# Sheet1.net
KiCad netlist of a schematic drawn in Altium Designer
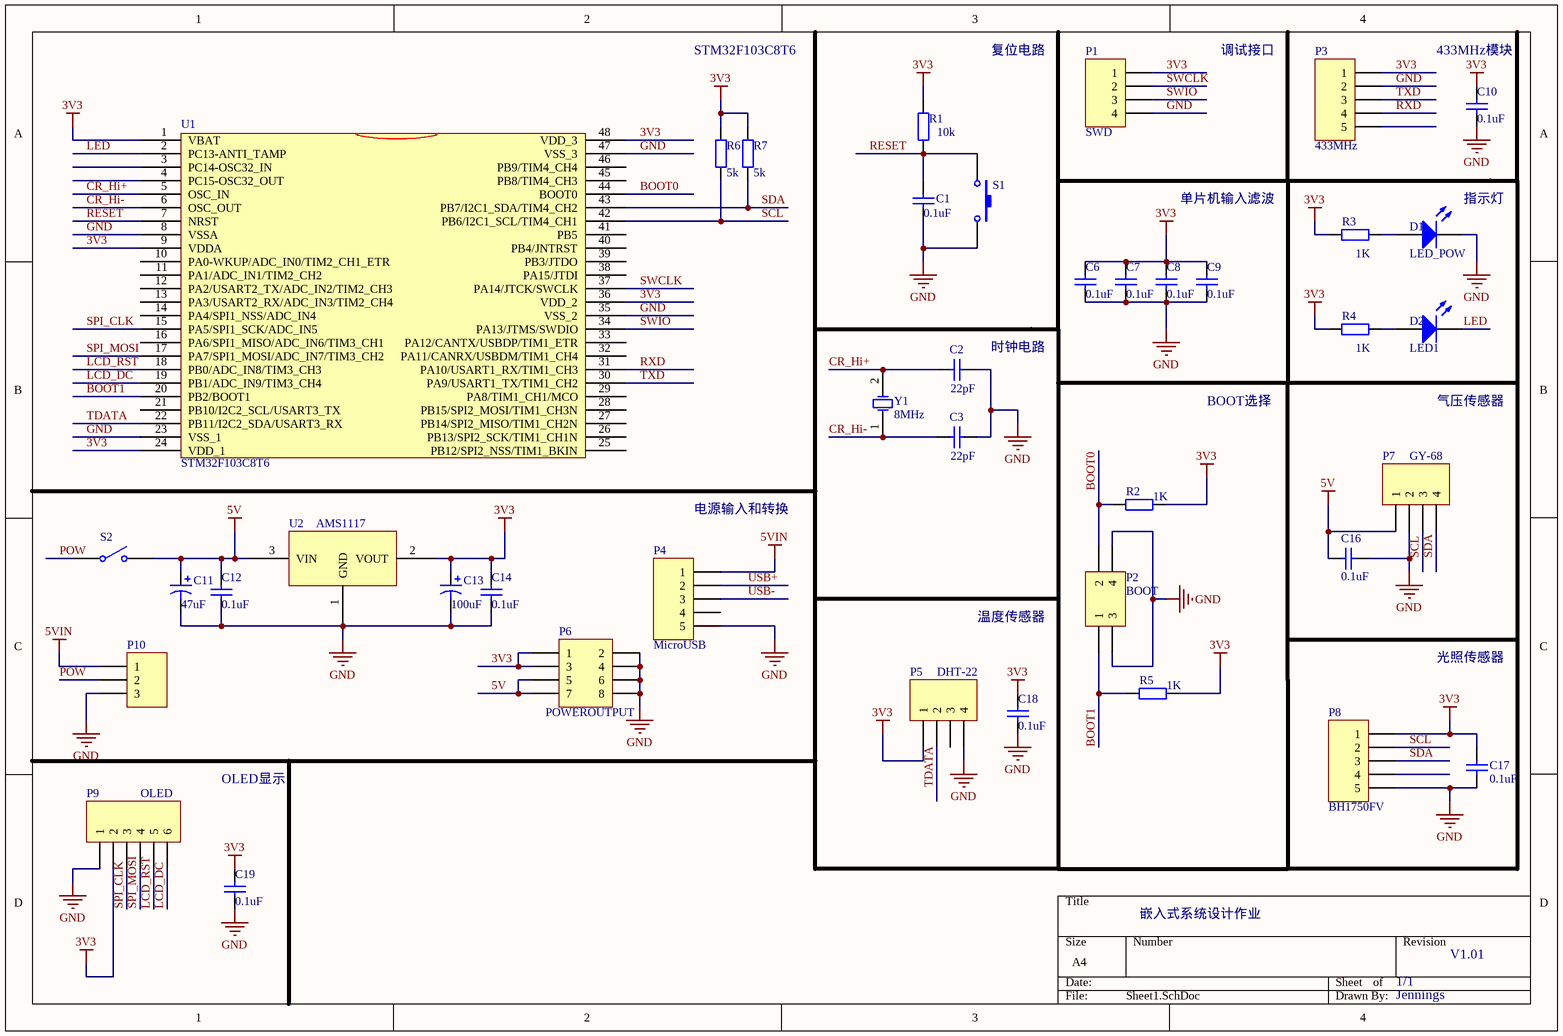
[diagram p0: Sheet1.SchDoc]

(export (version "E")
  (design (tool "Eeschema 10.0.6"))
  (components
    (comp (ref "C1")
      (value "0.1uF")
      (footprint "0402")
      (description "Capacitor")
      (fields (field (name "Comment") "Cap") (field (name "PUBLISHER") "Altium Limited"))
      (libsource (lib "Miscellaneous Devices") (part "Cap"))
    )
    (comp (ref "C2")
      (value "22pF")
      (footprint "0603-1")
      (description "Capacitor")
      (fields (field (name "Comment") "Cap") (field (name "PUBLISHER") "Altium Limited"))
      (libsource (lib "Miscellaneous Devices") (part "Cap"))
    )
    (comp (ref "C3")
      (value "22pF")
      (footprint "0603-1")
      (description "Capacitor")
      (fields (field (name "Comment") "Cap") (field (name "PUBLISHER") "Altium Limited"))
      (libsource (lib "Miscellaneous Devices") (part "Cap"))
    )
    (comp (ref "C6")
      (value "0.1uF")
      (footprint "0402")
      (description "Capacitor")
      (fields (field (name "Comment") "Cap") (field (name "PUBLISHER") "Altium Limited"))
      (libsource (lib "Miscellaneous Devices") (part "Cap"))
    )
    (comp (ref "C7")
      (value "0.1uF")
      (footprint "0402")
      (description "Capacitor")
      (fields (field (name "Comment") "Cap") (field (name "PUBLISHER") "Altium Limited"))
      (libsource (lib "Miscellaneous Devices") (part "Cap"))
    )
    (comp (ref "C8")
      (value "0.1uF")
      (footprint "0402")
      (description "Capacitor")
      (fields (field (name "Comment") "Cap") (field (name "PUBLISHER") "Altium Limited"))
      (libsource (lib "Miscellaneous Devices") (part "Cap"))
    )
    (comp (ref "C9")
      (value "0.1uF")
      (footprint "0402")
      (description "Capacitor")
      (fields (field (name "Comment") "Cap") (field (name "PUBLISHER") "Altium Limited"))
      (libsource (lib "Miscellaneous Devices") (part "Cap"))
    )
    (comp (ref "C10")
      (value "0.1uF")
      (footprint "0402")
      (description "Capacitor")
      (fields (field (name "Comment") "Cap") (field (name "PUBLISHER") "Altium Limited"))
      (libsource (lib "Miscellaneous Devices") (part "Cap"))
    )
    (comp (ref "C11")
      (value "47uF")
      (footprint "CAP-7343")
      (description "Polarized Capacitor (Radial)")
      (fields (field (name "Comment") "Cap Pol1") (field (name "PUBLISHER") "Altium Limited"))
      (libsource (lib "Miscellaneous Devices") (part "Cap Pol1"))
    )
    (comp (ref "C12")
      (value "0.1uF")
      (footprint "0402")
      (description "Capacitor")
      (fields (field (name "Comment") "Cap") (field (name "PUBLISHER") "Altium Limited"))
      (libsource (lib "Miscellaneous Devices") (part "Cap"))
    )
    (comp (ref "C13")
      (value "100uF")
      (footprint "CAP-6032")
      (description "Polarized Capacitor (Radial)")
      (fields (field (name "Comment") "Cap Pol1") (field (name "PUBLISHER") "Altium Limited"))
      (libsource (lib "Miscellaneous Devices") (part "Cap Pol1"))
    )
    (comp (ref "C14")
      (value "0.1uF")
      (footprint "0402")
      (description "Capacitor")
      (fields (field (name "Comment") "Cap") (field (name "PUBLISHER") "Altium Limited"))
      (libsource (lib "Miscellaneous Devices") (part "Cap"))
    )
    (comp (ref "C16")
      (value "0.1uF")
      (footprint "0402")
      (description "Capacitor")
      (fields (field (name "Comment") "Cap") (field (name "PUBLISHER") "Altium Limited"))
      (libsource (lib "Miscellaneous Devices") (part "Cap"))
    )
    (comp (ref "C17")
      (value "0.1uF")
      (footprint "0402")
      (description "Capacitor")
      (fields (field (name "Comment") "Cap") (field (name "PUBLISHER") "Altium Limited"))
      (libsource (lib "Miscellaneous Devices") (part "Cap"))
    )
    (comp (ref "C18")
      (value "0.1uF")
      (footprint "0402")
      (description "Capacitor")
      (fields (field (name "Comment") "Cap") (field (name "PUBLISHER") "Altium Limited"))
      (libsource (lib "Miscellaneous Devices") (part "Cap"))
    )
    (comp (ref "C19")
      (value "0.1uF")
      (footprint "0402")
      (description "Capacitor")
      (fields (field (name "Comment") "Cap") (field (name "PUBLISHER") "Altium Limited"))
      (libsource (lib "Miscellaneous Devices") (part "Cap"))
    )
    (comp (ref "D1")
      (value "LED_POW")
      (footprint "0402")
      (description "Typical RED, GREEN, YELLOW, AMBER GaAs LED")
      (fields (field (name "PUBLISHER") "Altium Limited"))
      (libsource (lib "Miscellaneous Devices") (part "LED2"))
    )
    (comp (ref "D2")
      (value "LED1")
      (footprint "0402")
      (description "Typical RED, GREEN, YELLOW, AMBER GaAs LED")
      (fields (field (name "PUBLISHER") "Altium Limited"))
      (libsource (lib "Miscellaneous Devices") (part "LED2"))
    )
    (comp (ref "P1")
      (value "SWD")
      (footprint "HDR1X4")
      (description "Header, 4-Pin")
      (fields (field (name "PUBLISHER") "Altium Limited"))
      (libsource (lib "Miscellaneous Connectors") (part "Header 4"))
    )
    (comp (ref "P2")
      (value "BOOT")
      (footprint "HDR2X2")
      (description "Header, 2-Pin, Dual row")
      (fields (field (name "PUBLISHER") "Altium Limited"))
      (libsource (lib "Miscellaneous Connectors") (part "Header 2X2"))
    )
    (comp (ref "P3")
      (value "433MHz")
      (footprint "HDR1X5")
      (description "Header, 5-Pin")
      (fields (field (name "PUBLISHER") "Altium Limited"))
      (libsource (lib "Miscellaneous Connectors") (part "Header 5"))
    )
    (comp (ref "P4")
      (value "MicroUSB")
      (footprint "Micro USB:Micro_USB")
      (description "Header, 5-Pin")
      (fields (field (name "PUBLISHER") "Altium Limited"))
      (libsource (lib "Miscellaneous Connectors") (part "Header 5"))
    )
    (comp (ref "P5")
      (value "DHT-22")
      (footprint "DHT22")
      (description "Header, 4-Pin")
      (fields (field (name "PUBLISHER") "Altium Limited"))
      (libsource (lib "") (part "Header 4_1"))
    )
    (comp (ref "P6")
      (value "POWEROUTPUT")
      (footprint "HDR2X4")
      (description "Header, 4-Pin, Dual row")
      (fields (field (name "PUBLISHER") "Altium Limited"))
      (libsource (lib "Miscellaneous Connectors") (part "Header 4X2"))
    )
    (comp (ref "P7")
      (value "GY-68")
      (footprint "BMP180MD")
      (description "Header, 4-Pin")
      (fields (field (name "PUBLISHER") "Altium Limited"))
      (libsource (lib "") (part "Header 4_1"))
    )
    (comp (ref "P8")
      (value "BH1750FV")
      (footprint "GY-30MD")
      (description "Header, 5-Pin")
      (fields (field (name "PUBLISHER") "Altium Limited"))
      (libsource (lib "Miscellaneous Connectors") (part "Header 5"))
    )
    (comp (ref "P9")
      (value "OLED")
      (footprint "OLED0.96")
      (description "Header, 6-Pin")
      (fields (field (name "PUBLISHER") "Altium Limited"))
      (libsource (lib "Miscellaneous Connectors") (part "Header 6"))
    )
    (comp (ref "P10")
      (value "Header 3")
      (footprint "HDR1X3")
      (description "Header, 3-Pin")
      (fields (field (name "PUBLISHER") "Altium Limited"))
      (libsource (lib "Miscellaneous Connectors") (part "Header 3"))
    )
    (comp (ref "R1")
      (value "10k")
      (footprint "0603-1")
      (description "Resistor")
      (fields (field (name "Comment") "Res2") (field (name "PUBLISHER") "Altium Limited"))
      (libsource (lib "") (part "Res2_1"))
    )
    (comp (ref "R2")
      (value "1K")
      (footprint "0402")
      (description "Resistor")
      (fields (field (name "Comment") "Res2") (field (name "PUBLISHER") "Altium Limited"))
      (libsource (lib "Miscellaneous Devices") (part "Res2"))
    )
    (comp (ref "R3")
      (value "1K")
      (footprint "0402")
      (description "Resistor")
      (fields (field (name "Comment") "Res2") (field (name "PUBLISHER") "Altium Limited"))
      (libsource (lib "Miscellaneous Devices") (part "Res2"))
    )
    (comp (ref "R4")
      (value "1K")
      (footprint "0402")
      (description "Resistor")
      (fields (field (name "Comment") "Res2") (field (name "PUBLISHER") "Altium Limited"))
      (libsource (lib "Miscellaneous Devices") (part "Res2"))
    )
    (comp (ref "R5")
      (value "1K")
      (footprint "0402")
      (description "Resistor")
      (fields (field (name "Comment") "Res2") (field (name "PUBLISHER") "Altium Limited"))
      (libsource (lib "Miscellaneous Devices") (part "Res2"))
    )
    (comp (ref "R6")
      (value "5k")
      (footprint "0603-1")
      (description "Resistor")
      (fields (field (name "Comment") "Res2") (field (name "PUBLISHER") "Altium Limited"))
      (libsource (lib "") (part "Res2_1"))
    )
    (comp (ref "R7")
      (value "5k")
      (footprint "0603-1")
      (description "Resistor")
      (fields (field (name "Comment") "Res2") (field (name "PUBLISHER") "Altium Limited"))
      (libsource (lib "") (part "Res2_1"))
    )
    (comp (ref "S1")
      (value "SW-PB")
      (footprint "SW_PB4_A1")
      (description "Switch")
      (fields (field (name "PUBLISHER") "Altium Limited"))
      (libsource (lib "Miscellaneous Devices") (part "SW-PB"))
    )
    (comp (ref "S2")
      (value "SW_POWER")
      (footprint "SW_Small")
      (description "Single-Pole, Single-Throw Switch")
      (fields (field (name "PUBLISHER") "Altium Limited"))
      (libsource (lib "Miscellaneous Devices") (part "SW-SPST"))
    )
    (comp (ref "U1")
      (value "STM32F103C8T6")
      (footprint "LQFP48S")
      (libsource (lib "stm32") (part "STM32F103C6"))
    )
    (comp (ref "U2") (value "AMS1117") (footprint "SOT-223") (libsource (lib "Schlib1") (part "AMS1117")))
    (comp (ref "Y1")
      (value "8MHz")
      (footprint "XTAL-8M")
      (description "Crystal Oscillator")
      (fields (field (name "PUBLISHER") "Altium Limited"))
      (libsource (lib "Miscellaneous Devices") (part "XTAL"))
    )
  )
  (nets
    (net (code "1") (name "/BOOT0") (class "Default")
      (node (ref "P2") (pin "2") (pinfunction "2_2") (pintype "passive"))
      (node (ref "R2") (pin "1") (pinfunction "1_1") (pintype "passive"))
      (node (ref "U1") (pin "44") (pinfunction "BOOT0_44") (pintype "passive"))
    )
    (net (code "2") (name "/BOOT1") (class "Default")
      (node (ref "P2") (pin "1") (pinfunction "1_1") (pintype "passive"))
      (node (ref "R5") (pin "1") (pinfunction "1_1") (pintype "passive"))
      (node (ref "U1") (pin "20") (pinfunction "PB2/BOOT1_20") (pintype "passive"))
    )
    (net (code "3") (name "/CR_Hi+") (class "Default")
      (node (ref "C2") (pin "1") (pinfunction "1_1") (pintype "passive"))
      (node (ref "U1") (pin "5") (pinfunction "OSC_IN_5") (pintype "passive"))
      (node (ref "Y1") (pin "2") (pinfunction "OSC2_2") (pintype "passive"))
    )
    (net (code "4") (name "/CR_Hi-") (class "Default")
      (node (ref "C3") (pin "1") (pinfunction "1_1") (pintype "passive"))
      (node (ref "U1") (pin "6") (pinfunction "OSC_OUT_6") (pintype "passive"))
      (node (ref "Y1") (pin "1") (pinfunction "OSC1_1") (pintype "passive"))
    )
    (net (code "5") (name "/LCD_DC") (class "Default")
      (node (ref "P9") (pin "6") (pinfunction "6_6") (pintype "passive"))
      (node (ref "U1") (pin "19") (pinfunction "PB1/ADC_IN9/TIM3_CH4_19") (pintype "passive"))
    )
    (net (code "6") (name "/LCD_RST") (class "Default")
      (node (ref "P9") (pin "5") (pinfunction "5_5") (pintype "passive"))
      (node (ref "U1") (pin "18") (pinfunction "PB0/ADC_IN8/TIM3_CH3_18") (pintype "passive"))
    )
    (net (code "7") (name "/LED") (class "Default")
      (node (ref "D2") (pin "2") (pinfunction "K_2") (pintype "passive"))
      (node (ref "U1") (pin "2") (pinfunction "PC13-ANTI_TAMP_2") (pintype "passive"))
    )
    (net (code "8") (name "/POW") (class "Default")
      (node (ref "P10") (pin "2") (pinfunction "2_2") (pintype "passive"))
      (node (ref "S2") (pin "1") (pinfunction "COMMON_1") (pintype "passive"))
    )
    (net (code "9") (name "/RESET") (class "Default")
      (node (ref "C1") (pin "2") (pinfunction "2_2") (pintype "passive"))
      (node (ref "R1") (pin "1") (pinfunction "1_1") (pintype "passive"))
      (node (ref "S1") (pin "1") (pinfunction "1_1") (pintype "passive"))
      (node (ref "U1") (pin "7") (pinfunction "NRST_7") (pintype "passive"))
    )
    (net (code "10") (name "/RXD") (class "Default")
      (node (ref "P3") (pin "4") (pinfunction "4_4") (pintype "passive"))
      (node (ref "U1") (pin "31") (pinfunction "PA10/USART1_RX/TIM1_CH3_31") (pintype "passive"))
    )
    (net (code "11") (name "/SCL") (class "Default")
      (node (ref "P7") (pin "3") (pinfunction "3_3") (pintype "passive"))
      (node (ref "P8") (pin "2") (pinfunction "2_2") (pintype "passive"))
      (node (ref "R6") (pin "1") (pinfunction "1_1") (pintype "passive"))
      (node (ref "U1") (pin "42") (pinfunction "PB6/I2C1_SCL/TIM4_CH1_42") (pintype "passive"))
    )
    (net (code "12") (name "/SDA") (class "Default")
      (node (ref "P7") (pin "4") (pinfunction "4_4") (pintype "passive"))
      (node (ref "P8") (pin "3") (pinfunction "3_3") (pintype "passive"))
      (node (ref "R7") (pin "1") (pinfunction "1_1") (pintype "passive"))
      (node (ref "U1") (pin "43") (pinfunction "PB7/I2C1_SDA/TIM4_CH2_43") (pintype "passive"))
    )
    (net (code "13") (name "/SPI_CLK") (class "Default")
      (node (ref "P9") (pin "3") (pinfunction "3_3") (pintype "passive"))
      (node (ref "U1") (pin "15") (pinfunction "PA5/SPI1_SCK/ADC_IN5_15") (pintype "passive"))
    )
    (net (code "14") (name "/SPI_MOSI") (class "Default")
      (node (ref "P9") (pin "4") (pinfunction "4_4") (pintype "passive"))
      (node (ref "U1") (pin "17") (pinfunction "PA7/SPI1_MOSI/ADC_IN7/TIM3_CH2_17") (pintype "passive"))
    )
    (net (code "15") (name "/SWCLK") (class "Default")
      (node (ref "P1") (pin "2") (pinfunction "2_2") (pintype "passive"))
      (node (ref "U1") (pin "37") (pinfunction "PA14/JTCK/SWCLK_37") (pintype "passive"))
    )
    (net (code "16") (name "/SWIO") (class "Default")
      (node (ref "P1") (pin "3") (pinfunction "3_3") (pintype "passive"))
      (node (ref "U1") (pin "34") (pinfunction "PA13/JTMS/SWDIO_34") (pintype "passive"))
    )
    (net (code "17") (name "/TDATA") (class "Default")
      (node (ref "P5") (pin "2") (pinfunction "2_2") (pintype "passive"))
      (node (ref "U1") (pin "22") (pinfunction "PB11/I2C2_SDA/USART3_RX_22") (pintype "passive"))
    )
    (net (code "18") (name "/TXD") (class "Default")
      (node (ref "P3") (pin "3") (pinfunction "3_3") (pintype "passive"))
      (node (ref "U1") (pin "30") (pinfunction "PA9/USART1_TX/TIM1_CH2_30") (pintype "passive"))
    )
    (net (code "19") (name "/USB+") (class "Default")
      (node (ref "P4") (pin "2") (pinfunction "2_2") (pintype "passive"))
    )
    (net (code "20") (name "/USB-") (class "Default")
      (node (ref "P4") (pin "3") (pinfunction "3_3") (pintype "passive"))
    )
    (net (code "21") (name "3V3") (class "Default")
      (node (ref "C10") (pin "2") (pinfunction "2_2") (pintype "passive"))
      (node (ref "C13") (pin "1") (pinfunction "1_1") (pintype "passive"))
      (node (ref "C14") (pin "2") (pinfunction "2_2") (pintype "passive"))
      (node (ref "C17") (pin "1") (pinfunction "1_1") (pintype "passive"))
      (node (ref "C18") (pin "2") (pinfunction "2_2") (pintype "passive"))
      (node (ref "C19") (pin "2") (pinfunction "2_2") (pintype "passive"))
      (node (ref "C6") (pin "2") (pinfunction "2_2") (pintype "passive"))
      (node (ref "C7") (pin "2") (pinfunction "2_2") (pintype "passive"))
      (node (ref "C8") (pin "2") (pinfunction "2_2") (pintype "passive"))
      (node (ref "C9") (pin "2") (pinfunction "2_2") (pintype "passive"))
      (node (ref "P1") (pin "1") (pinfunction "1_1") (pintype "passive"))
      (node (ref "P3") (pin "1") (pinfunction "1_1") (pintype "passive"))
      (node (ref "P5") (pin "1") (pinfunction "1_1") (pintype "passive"))
      (node (ref "P6") (pin "1") (pinfunction "1_1") (pintype "passive"))
      (node (ref "P6") (pin "3") (pinfunction "3_3") (pintype "passive"))
      (node (ref "P8") (pin "1") (pinfunction "1_1") (pintype "passive"))
      (node (ref "P9") (pin "2") (pinfunction "2_2") (pintype "passive"))
      (node (ref "R1") (pin "2") (pinfunction "2_2") (pintype "passive"))
      (node (ref "R2") (pin "2") (pinfunction "2_2") (pintype "passive"))
      (node (ref "R3") (pin "1") (pinfunction "1_1") (pintype "passive"))
      (node (ref "R4") (pin "1") (pinfunction "1_1") (pintype "passive"))
      (node (ref "R5") (pin "2") (pinfunction "2_2") (pintype "passive"))
      (node (ref "R6") (pin "2") (pinfunction "2_2") (pintype "passive"))
      (node (ref "R7") (pin "2") (pinfunction "2_2") (pintype "passive"))
      (node (ref "U1") (pin "1") (pinfunction "VBAT_1") (pintype "passive"))
      (node (ref "U1") (pin "24") (pinfunction "VDD_1_24") (pintype "passive"))
      (node (ref "U1") (pin "36") (pinfunction "VDD_2_36") (pintype "passive"))
      (node (ref "U1") (pin "48") (pinfunction "VDD_3_48") (pintype "passive"))
      (node (ref "U1") (pin "9") (pinfunction "VDDA_9") (pintype "passive"))
      (node (ref "U2") (pin "2") (pinfunction "VOUT_2") (pintype "passive"))
    )
    (net (code "22") (name "5V") (class "Default")
      (node (ref "C11") (pin "1") (pinfunction "1_1") (pintype "passive"))
      (node (ref "C12") (pin "2") (pinfunction "2_2") (pintype "passive"))
      (node (ref "C16") (pin "2") (pinfunction "2_2") (pintype "passive"))
      (node (ref "P6") (pin "5") (pinfunction "5_5") (pintype "passive"))
      (node (ref "P6") (pin "7") (pinfunction "7_7") (pintype "passive"))
      (node (ref "P7") (pin "1") (pinfunction "1_1") (pintype "passive"))
      (node (ref "S2") (pin "2") (pinfunction "NO_2") (pintype "passive"))
      (node (ref "U2") (pin "3") (pinfunction "VIN_3") (pintype "passive"))
    )
    (net (code "23") (name "5VIN") (class "Default")
      (node (ref "P10") (pin "1") (pinfunction "1_1") (pintype "passive"))
      (node (ref "P4") (pin "1") (pinfunction "1_1") (pintype "passive"))
    )
    (net (code "24") (name "GND") (class "Default")
      (node (ref "C1") (pin "1") (pinfunction "1_1") (pintype "passive"))
      (node (ref "C10") (pin "1") (pinfunction "1_1") (pintype "passive"))
      (node (ref "C11") (pin "2") (pinfunction "2_2") (pintype "passive"))
      (node (ref "C12") (pin "1") (pinfunction "1_1") (pintype "passive"))
      (node (ref "C13") (pin "2") (pinfunction "2_2") (pintype "passive"))
      (node (ref "C14") (pin "1") (pinfunction "1_1") (pintype "passive"))
      (node (ref "C16") (pin "1") (pinfunction "1_1") (pintype "passive"))
      (node (ref "C17") (pin "2") (pinfunction "2_2") (pintype "passive"))
      (node (ref "C18") (pin "1") (pinfunction "1_1") (pintype "passive"))
      (node (ref "C19") (pin "1") (pinfunction "1_1") (pintype "passive"))
      (node (ref "C2") (pin "2") (pinfunction "2_2") (pintype "passive"))
      (node (ref "C3") (pin "2") (pinfunction "2_2") (pintype "passive"))
      (node (ref "C6") (pin "1") (pinfunction "1_1") (pintype "passive"))
      (node (ref "C7") (pin "1") (pinfunction "1_1") (pintype "passive"))
      (node (ref "C8") (pin "1") (pinfunction "1_1") (pintype "passive"))
      (node (ref "C9") (pin "1") (pinfunction "1_1") (pintype "passive"))
      (node (ref "D1") (pin "2") (pinfunction "K_2") (pintype "passive"))
      (node (ref "P1") (pin "4") (pinfunction "4_4") (pintype "passive"))
      (node (ref "P10") (pin "3") (pinfunction "3_3") (pintype "passive"))
      (node (ref "P2") (pin "3") (pinfunction "3_3") (pintype "passive"))
      (node (ref "P2") (pin "4") (pinfunction "4_4") (pintype "passive"))
      (node (ref "P3") (pin "2") (pinfunction "2_2") (pintype "passive"))
      (node (ref "P4") (pin "5") (pinfunction "5_5") (pintype "passive"))
      (node (ref "P5") (pin "4") (pinfunction "4_4") (pintype "passive"))
      (node (ref "P6") (pin "2") (pinfunction "2_2") (pintype "passive"))
      (node (ref "P6") (pin "4") (pinfunction "4_4") (pintype "passive"))
      (node (ref "P6") (pin "6") (pinfunction "6_6") (pintype "passive"))
      (node (ref "P6") (pin "8") (pinfunction "8_8") (pintype "passive"))
      (node (ref "P7") (pin "2") (pinfunction "2_2") (pintype "passive"))
      (node (ref "P8") (pin "5") (pinfunction "5_5") (pintype "passive"))
      (node (ref "P9") (pin "1") (pinfunction "1_1") (pintype "passive"))
      (node (ref "S1") (pin "2") (pinfunction "2_2") (pintype "passive"))
      (node (ref "U1") (pin "23") (pinfunction "VSS_1_23") (pintype "passive"))
      (node (ref "U1") (pin "35") (pinfunction "VSS_2_35") (pintype "passive"))
      (node (ref "U1") (pin "47") (pinfunction "VSS_3_47") (pintype "passive"))
      (node (ref "U1") (pin "8") (pinfunction "VSSA_8") (pintype "passive"))
      (node (ref "U2") (pin "1") (pinfunction "GND_1") (pintype "passive"))
    )
    (net (code "25") (name "Net-(D1-A)") (class "Default")
      (node (ref "D1") (pin "1") (pinfunction "A_1") (pintype "passive"))
      (node (ref "R3") (pin "2") (pinfunction "2_2") (pintype "passive"))
    )
    (net (code "26") (name "Net-(D2-A)") (class "Default")
      (node (ref "D2") (pin "1") (pinfunction "A_1") (pintype "passive"))
      (node (ref "R4") (pin "2") (pinfunction "2_2") (pintype "passive"))
    )
    (net (code "27") (name "unconnected-(P3-Pad5)") (class "Default")
      (node (ref "P3") (pin "5") (pinfunction "5_5") (pintype "passive"))
    )
    (net (code "28") (name "unconnected-(P4-Pad4)") (class "Default")
      (node (ref "P4") (pin "4") (pinfunction "4_4") (pintype "passive"))
    )
    (net (code "29") (name "unconnected-(P5-Pad3)") (class "Default")
      (node (ref "P5") (pin "3") (pinfunction "3_3") (pintype "passive"))
    )
    (net (code "30") (name "unconnected-(P8-Pad4)") (class "Default")
      (node (ref "P8") (pin "4") (pinfunction "4_4") (pintype "passive"))
    )
    (net (code "31") (name "unconnected-(U1-PA0-WKUP{slash}ADC_IN0{slash}TIM2_CH1_ETR-Pad10)") (class "Default")
      (node (ref "U1") (pin "10") (pinfunction "PA0-WKUP/ADC_IN0/TIM2_CH1_ETR_10") (pintype "passive"))
    )
    (net (code "32") (name "unconnected-(U1-PA1{slash}ADC_IN1{slash}TIM2_CH2-Pad11)") (class "Default")
      (node (ref "U1") (pin "11") (pinfunction "PA1/ADC_IN1/TIM2_CH2_11") (pintype "passive"))
    )
    (net (code "33") (name "unconnected-(U1-PA2{slash}USART2_TX{slash}ADC_IN2{slash}TIM2_CH3-Pad12)") (class "Default")
      (node (ref "U1") (pin "12") (pinfunction "PA2/USART2_TX/ADC_IN2/TIM2_CH3_12") (pintype "passive"))
    )
    (net (code "34") (name "unconnected-(U1-PA3{slash}USART2_RX{slash}ADC_IN3{slash}TIM2_CH4-Pad13)") (class "Default")
      (node (ref "U1") (pin "13") (pinfunction "PA3/USART2_RX/ADC_IN3/TIM2_CH4_13") (pintype "passive"))
    )
    (net (code "35") (name "unconnected-(U1-PA4{slash}SPI1_NSS{slash}ADC_IN4-Pad14)") (class "Default")
      (node (ref "U1") (pin "14") (pinfunction "PA4/SPI1_NSS/ADC_IN4_14") (pintype "passive"))
    )
    (net (code "36") (name "unconnected-(U1-PA6{slash}SPI1_MISO{slash}ADC_IN6{slash}TIM3_CH1-Pad16)") (class "Default")
      (node (ref "U1") (pin "16") (pinfunction "PA6/SPI1_MISO/ADC_IN6/TIM3_CH1_16") (pintype "passive"))
    )
    (net (code "37") (name "unconnected-(U1-PA8{slash}TIM1_CH1{slash}MCO-Pad29)") (class "Default")
      (node (ref "U1") (pin "29") (pinfunction "PA8/TIM1_CH1/MCO_29") (pintype "passive"))
    )
    (net (code "38") (name "unconnected-(U1-PA11{slash}CANRX{slash}USBDM{slash}TIM1_CH4-Pad32)") (class "Default")
      (node (ref "U1") (pin "32") (pinfunction "PA11/CANRX/USBDM/TIM1_CH4_32") (pintype "passive"))
    )
    (net (code "39") (name "unconnected-(U1-PA12{slash}CANTX{slash}USBDP{slash}TIM1_ETR-Pad33)") (class "Default")
      (node (ref "U1") (pin "33") (pinfunction "PA12/CANTX/USBDP/TIM1_ETR_33") (pintype "passive"))
    )
    (net (code "40") (name "unconnected-(U1-PA15{slash}JTDI-Pad38)") (class "Default")
      (node (ref "U1") (pin "38") (pinfunction "PA15/JTDI_38") (pintype "passive"))
    )
    (net (code "41") (name "unconnected-(U1-PB3{slash}JTDO-Pad39)") (class "Default")
      (node (ref "U1") (pin "39") (pinfunction "PB3/JTDO_39") (pintype "passive"))
    )
    (net (code "42") (name "unconnected-(U1-PB4{slash}JNTRST-Pad40)") (class "Default")
      (node (ref "U1") (pin "40") (pinfunction "PB4/JNTRST_40") (pintype "passive"))
    )
    (net (code "43") (name "unconnected-(U1-PB5-Pad41)") (class "Default")
      (node (ref "U1") (pin "41") (pinfunction "PB5_41") (pintype "passive"))
    )
    (net (code "44") (name "unconnected-(U1-PB8{slash}TIM4_CH3-Pad45)") (class "Default")
      (node (ref "U1") (pin "45") (pinfunction "PB8/TIM4_CH3_45") (pintype "passive"))
    )
    (net (code "45") (name "unconnected-(U1-PB9{slash}TIM4_CH4-Pad46)") (class "Default")
      (node (ref "U1") (pin "46") (pinfunction "PB9/TIM4_CH4_46") (pintype "passive"))
    )
    (net (code "46") (name "unconnected-(U1-PB10{slash}I2C2_SCL{slash}USART3_TX-Pad21)") (class "Default")
      (node (ref "U1") (pin "21") (pinfunction "PB10/I2C2_SCL/USART3_TX_21") (pintype "passive"))
    )
    (net (code "47") (name "unconnected-(U1-PB12{slash}SPI2_NSS{slash}TIM1_BKIN-Pad25)") (class "Default")
      (node (ref "U1") (pin "25") (pinfunction "PB12/SPI2_NSS/TIM1_BKIN_25") (pintype "passive"))
    )
    (net (code "48") (name "unconnected-(U1-PB13{slash}SPI2_SCK{slash}TIM1_CH1N-Pad26)") (class "Default")
      (node (ref "U1") (pin "26") (pinfunction "PB13/SPI2_SCK/TIM1_CH1N_26") (pintype "passive"))
    )
    (net (code "49") (name "unconnected-(U1-PB14{slash}SPI2_MISO{slash}TIM1_CH2N-Pad27)") (class "Default")
      (node (ref "U1") (pin "27") (pinfunction "PB14/SPI2_MISO/TIM1_CH2N_27") (pintype "passive"))
    )
    (net (code "50") (name "unconnected-(U1-PB15{slash}SPI2_MOSI{slash}TIM1_CH3N-Pad28)") (class "Default")
      (node (ref "U1") (pin "28") (pinfunction "PB15/SPI2_MOSI/TIM1_CH3N_28") (pintype "passive"))
    )
    (net (code "51") (name "unconnected-(U1-PC14-OSC32_IN-Pad3)") (class "Default")
      (node (ref "U1") (pin "3") (pinfunction "PC14-OSC32_IN_3") (pintype "passive"))
    )
    (net (code "52") (name "unconnected-(U1-PC15-OSC32_OUT-Pad4)") (class "Default")
      (node (ref "U1") (pin "4") (pinfunction "PC15-OSC32_OUT_4") (pintype "passive"))
    )
  )
)
